# BOOST.net
KiCad netlist of a schematic drawn in Altium Designer
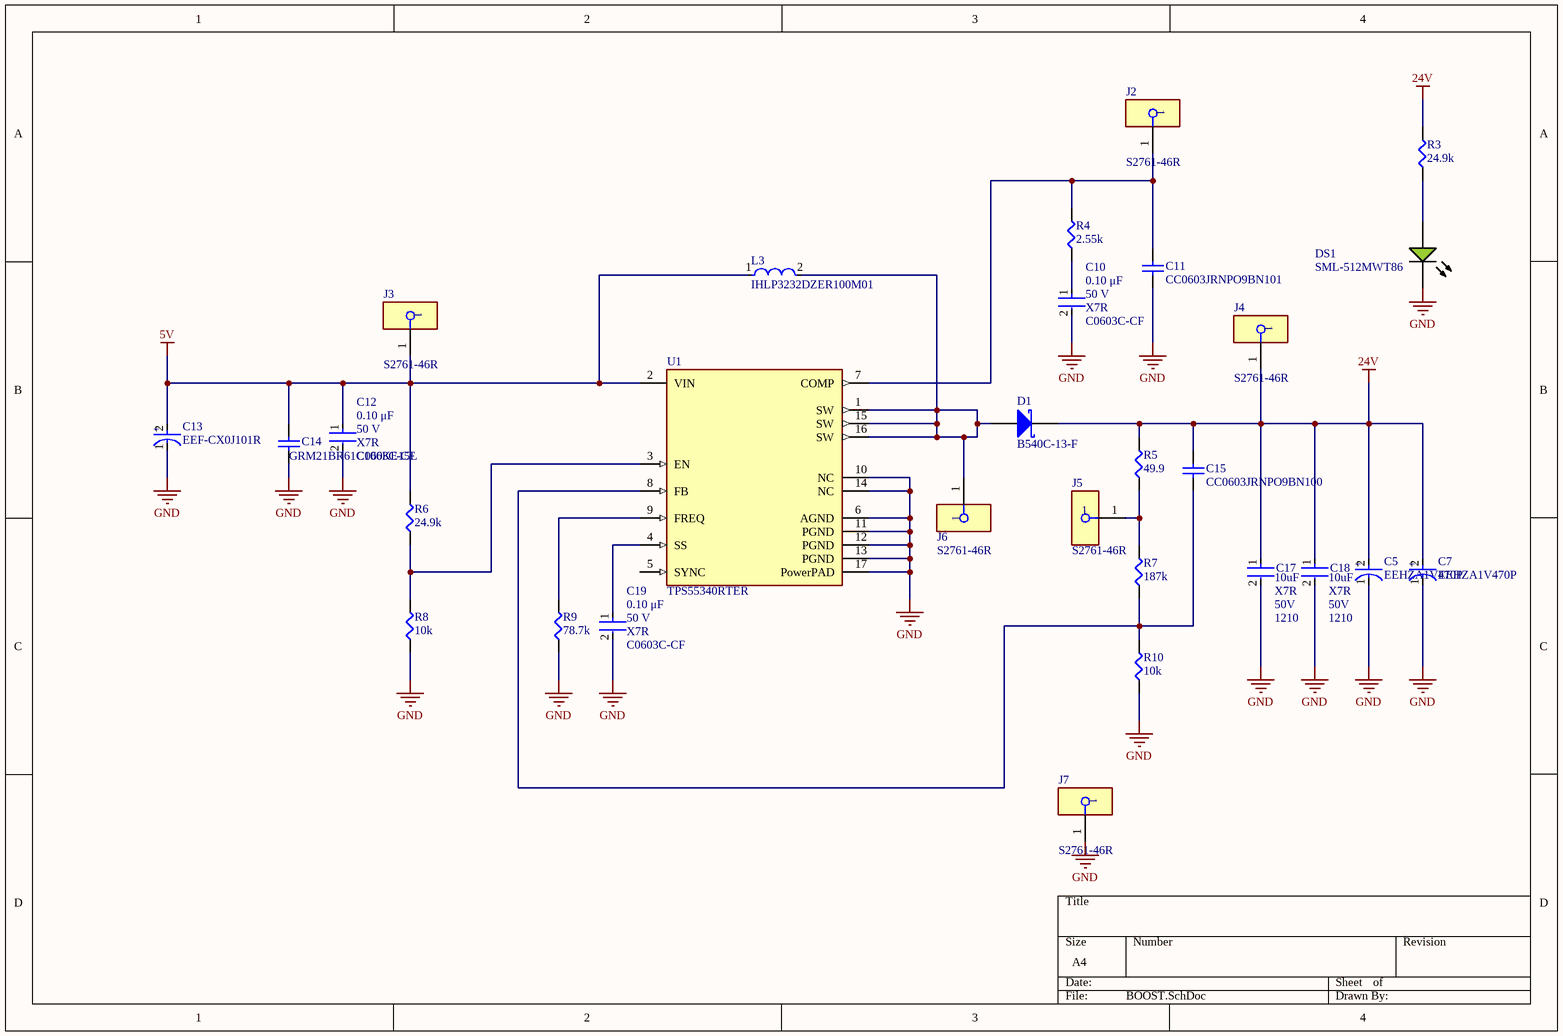
[diagram p0: BOOST.SchDoc]

(export (version "E")
  (design (tool "Eeschema 10.0.6"))
  (components
    (comp (ref "C5")
      (value "EEHZA1V470P")
      (footprint "FP-EEH-D-MFG")
      (description "Aluminum Hybrid Polymer Capacitors 47uF 20% 35V Life 10000Hours AEC-Q200 RADIAL SMT")
      (libsource (lib "Altium Content Vault") (part "a00bbbee19879c290e62620ae7e47b1"))
    )
    (comp (ref "C7")
      (value "EEHZA1V470P")
      (footprint "FP-EEH-D-MFG")
      (description "Aluminum Hybrid Polymer Capacitors 47uF 20% 35V Life 10000Hours AEC-Q200 RADIAL SMT")
      (libsource (lib "Altium Content Vault") (part "a00bbbee19879c290e62620ae7e47b1"))
    )
    (comp (ref "C10")
      (value "0.10 μF")
      (footprint "FP-C0603C-CF-MFG")
      (description "CAP CER 0.1UF 50V X7R 0603")
      (fields
        (field (name "TOLERANCE") "0.1")
        (field (name "MANUFACTURER") "KEMET")
        (field (name "PACKAGE") "C0603C-CF")
        (field (name "VOLTAGE RATING") "50 V")
        (field (name "TEMPERATURE CHARACTERISTIC") "X7R")
      )
      (libsource (lib "Altium Content Vault") (part "b4654b650e69147ec39a6b967a45e02"))
    )
    (comp (ref "C11")
      (value "CC0603JRNPO9BN101")
      (footprint "CAPC1608X90X40ML10T20")
      (description "Chip Capacitor, 100 pF, +/- 5%, 50 V, -55 to 125 degC, 0603 (1608 Metric), RoHS, Tape and Reel")
      (fields (field (name "TOLERANCE") "5%") (field (name "VOLTAGE") "50V"))
      (libsource (lib "Altium Content Vault") (part "CAP-NP-2"))
    )
    (comp (ref "C12")
      (value "0.10 μF")
      (footprint "FP-C0603C-CF-MFG")
      (description "CAP CER 0.1UF 50V X7R 0603")
      (fields
        (field (name "TOLERANCE") "0.1")
        (field (name "MANUFACTURER") "KEMET")
        (field (name "PACKAGE") "C0603C-CF")
        (field (name "VOLTAGE RATING") "50 V")
        (field (name "TEMPERATURE CHARACTERISTIC") "X7R")
      )
      (libsource (lib "Altium Content Vault") (part "b4654b650e69147ec39a6b967a45e02"))
    )
    (comp (ref "C13")
      (value "EEF-CX0J101R")
      (footprint "FP-CX-MFG")
      (description "CAP ALUM POLY 100UF 20% 6.3V SMD")
      (fields (field (name "VOLTAGE") "6.3V") (field (name "TOLERANCE") "20%"))
      (libsource (lib "Altium Content Vault") (part "a00bbbee19879c290e62620ae7e47b1"))
    )
    (comp (ref "C14")
      (value "GRM21BR61C106KE15L")
      (footprint "CAPC2013X135X50LL10T20")
      (fields (field (name "MANUFACTURER") "Murata"))
      (libsource (lib "Altium Content Vault") (part "CAP"))
    )
    (comp (ref "C15")
      (value "CC0603JRNPO9BN100")
      (footprint "CAPC1608X90X40ML10T20")
      (description "Chip Capacitor, 10 pF, +/- 5%, 50 V, -55 to 125 degC, 0603 (1608 Metric), RoHS, Tape and Reel")
      (fields (field (name "VOLTAGE") "50V") (field (name "TOLERANCE") "5%"))
      (libsource (lib "Altium Content Vault") (part "CAP-NP-2"))
    )
    (comp (ref "C17")
      (value "CL32B106KBJNNNE")
      (footprint "FP-CL32-IPC_C")
      (description "Cap Ceramic 10uF 50V X7R ±10% SMD 1210 +125°C Embossed T/R")
      (fields
        (field (name "CAPACITANCE") "10uF")
        (field (name "DIELECTRIC") "X7R")
        (field (name "VOLTAGE RATING (DC)") "50V")
        (field (name "CASE CODE (IMPERIAL)") "1210")
        (field (name "TOLERANCE") "10%")
        (field (name "VOLTAGE") "50V")
      )
      (libsource (lib "Altium Content Vault") (part "b4654b650e69147ec39a6b967a45e02"))
    )
    (comp (ref "C18")
      (value "CL32B106KBJNNNE")
      (footprint "FP-CL32-IPC_C")
      (description "Cap Ceramic 10uF 50V X7R ±10% SMD 1210 +125°C Embossed T/R")
      (fields
        (field (name "CAPACITANCE") "10uF")
        (field (name "DIELECTRIC") "X7R")
        (field (name "VOLTAGE RATING (DC)") "50V")
        (field (name "CASE CODE (IMPERIAL)") "1210")
        (field (name "TOLERANCE") "10%")
        (field (name "VOLTAGE") "50V")
      )
      (libsource (lib "Altium Content Vault") (part "b4654b650e69147ec39a6b967a45e02"))
    )
    (comp (ref "C19")
      (value "0.10 μF")
      (footprint "FP-C0603C-CF-MFG")
      (description "CAP CER 0.1UF 50V X7R 0603")
      (fields
        (field (name "TOLERANCE") "0.1")
        (field (name "MANUFACTURER") "KEMET")
        (field (name "PACKAGE") "C0603C-CF")
        (field (name "VOLTAGE RATING") "50 V")
        (field (name "TEMPERATURE CHARACTERISTIC") "X7R")
      )
      (libsource (lib "Altium Content Vault") (part "b4654b650e69147ec39a6b967a45e02"))
    )
    (comp (ref "D1")
      (value "B540C-13-F")
      (footprint "DIOD-B5X0C-2_L")
      (description "Schottky Barrier Rectifier, 5 A, 40 V, -55 to 125 degC, 2-Pin SMD, RoHS, Tape and Reel")
      (fields (field (name "MANUFACTURER") "DiodesIncorporated"))
      (libsource (lib "Altium Content Vault") (part "DSKY-KA-2"))
    )
    (comp (ref "DS1")
      (value "SML-512MWT86")
      (footprint "ROHM-SML-51X_V")
      (description "Yellow Green LED, 2.1 V, 20 mA, -30 to 85 degC, 2-Pin SMD, RoHS, Tape and Reel")
      (fields (field (name "MANUFACTURER") "Rohm"))
      (libsource (lib "Altium Content Vault") (part "LED-YELLOW-GREEN-AK-2"))
    )
    (comp (ref "J2")
      (value "S2761-46R")
      (footprint "FP-S2761-46R-MFG")
      (description "PC TEST POINT NATURAL")
      (libsource (lib "") (part "98815daf2f2c152b0c43f5ab9800df6_2"))
    )
    (comp (ref "J3")
      (value "S2761-46R")
      (footprint "FP-S2761-46R-MFG")
      (description "PC TEST POINT NATURAL")
      (libsource (lib "") (part "98815daf2f2c152b0c43f5ab9800df6_2"))
    )
    (comp (ref "J4")
      (value "S2761-46R")
      (footprint "FP-S2761-46R-MFG")
      (description "PC TEST POINT NATURAL")
      (libsource (lib "") (part "98815daf2f2c152b0c43f5ab9800df6_2"))
    )
    (comp (ref "J5")
      (value "S2761-46R")
      (footprint "FP-S2761-46R-MFG")
      (description "PC TEST POINT NATURAL")
      (libsource (lib "") (part "98815daf2f2c152b0c43f5ab9800df6_1"))
    )
    (comp (ref "J6")
      (value "S2761-46R")
      (footprint "FP-S2761-46R-MFG")
      (description "PC TEST POINT NATURAL")
      (libsource (lib "Altium Content Vault") (part "98815daf2f2c152b0c43f5ab9800df6"))
    )
    (comp (ref "J7")
      (value "S2761-46R")
      (footprint "FP-S2761-46R-MFG")
      (description "PC TEST POINT NATURAL")
      (libsource (lib "") (part "98815daf2f2c152b0c43f5ab9800df6_2"))
    )
    (comp (ref "L3")
      (value "IHLP3232DZER100M01")
      (footprint "FP-IHLP-3232DZ-FP_2_413x5-MFG")
      (description "FIXED IND 10UH 5.2A 59.9 MOHM")
      (fields (field (name "TOLERANCE") "20%"))
      (libsource (lib "Altium Content Vault") (part "725321dda6339637d4d059423bc1c3c"))
    )
    (comp (ref "R3")
      (value "24.9k")
      (footprint "SMD-0603-RES")
      (description "RES SMD 24.9K OHM 1% 1/10W 0603")
      (fields
        (field (name "PART NUMBER") "ERJ-3EKF2492V")
        (field (name "DIGI-KEY PART NUMBER") "P24.9KHCT-ND")
      )
      (libsource (lib "Panasonic_ERJ_0603") (part "ERJ-3EKF2492V"))
    )
    (comp (ref "R4")
      (value "2.55k")
      (footprint "SMD-0603-RES")
      (description "RES SMD 2.55K OHM 1% 1/10W 0603")
      (fields
        (field (name "PART NUMBER") "ERJ-3EKF2551V")
        (field (name "DIGI-KEY PART NUMBER") "P2.55KHCT-ND")
      )
      (libsource (lib "Panasonic_ERJ_0603") (part "ERJ-3EKF2551V"))
    )
    (comp (ref "R5")
      (value "49.9")
      (footprint "SMD-0603-RES")
      (description "RES SMD 49.9 OHM 1% 1/10W 0603")
      (fields
        (field (name "PART NUMBER") "ERJ-3EKF49R9V")
        (field (name "DIGI-KEY PART NUMBER") "P49.9HCT-ND")
      )
      (libsource (lib "Panasonic_ERJ_0603") (part "ERJ-3EKF49R9V"))
    )
    (comp (ref "R6")
      (value "24.9k")
      (footprint "SMD-0603-RES")
      (description "RES SMD 24.9K OHM 1% 1/10W 0603")
      (fields
        (field (name "PART NUMBER") "ERJ-3EKF2492V")
        (field (name "DIGI-KEY PART NUMBER") "P24.9KHCT-ND")
      )
      (libsource (lib "Panasonic_ERJ_0603") (part "ERJ-3EKF2492V"))
    )
    (comp (ref "R7")
      (value "187k")
      (footprint "SMD-0603-RES")
      (description "RES SMD 187K OHM 1% 1/10W 0603")
      (fields
        (field (name "PART NUMBER") "ERJ-3EKF1873V")
        (field (name "DIGI-KEY PART NUMBER") "P187KHCT-ND")
      )
      (libsource (lib "Panasonic_ERJ_0603") (part "ERJ-3EKF1873V"))
    )
    (comp (ref "R8")
      (value "10k")
      (footprint "SMD-0603-RES")
      (description "RES SMD 10K OHM 1% 1/10W 0603")
      (fields
        (field (name "PART NUMBER") "ERJ-3EKF1002V")
        (field (name "DIGI-KEY PART NUMBER") "P10.0KHCT-ND")
      )
      (libsource (lib "Panasonic_ERJ_0603") (part "ERJ-3EKF1002V"))
    )
    (comp (ref "R9")
      (value "78.7k")
      (footprint "SMD-0603-RES")
      (description "RES SMD 78.7K OHM 1% 1/10W 0603")
      (fields
        (field (name "PART NUMBER") "ERJ-3EKF7872V")
        (field (name "DIGI-KEY PART NUMBER") "P78.7KHCT-ND")
      )
      (libsource (lib "Panasonic_ERJ_0603") (part "ERJ-3EKF7872V"))
    )
    (comp (ref "R10")
      (value "10k")
      (footprint "SMD-0603-RES")
      (description "RES SMD 10K OHM 1% 1/10W 0603")
      (fields
        (field (name "PART NUMBER") "ERJ-3EKF1002V")
        (field (name "DIGI-KEY PART NUMBER") "P10.0KHCT-ND")
      )
      (libsource (lib "Panasonic_ERJ_0603") (part "ERJ-3EKF1002V"))
    )
    (comp (ref "U1")
      (value "TPS55340RTER")
      (footprint "FP-RTE0016C-IPC_A")
      (description "IC REG BOOST ADJ 5.25A 16WQFN")
      (libsource (lib "Altium Content Vault") (part "97752be00374b74295015ec96ff4d5f"))
    )
  )
  (nets
    (net (code "1") (name "5V") (class "Default")
      (node (ref "C12") (pin "1") (pinfunction "1_1") (pintype "passive"))
      (node (ref "C13") (pin "2") (pinfunction "A_2") (pintype "passive"))
      (node (ref "C14") (pin "2") (pinfunction "2_2") (pintype "passive"))
      (node (ref "J3") (pin "1") (pinfunction "1_1") (pintype "passive"))
      (node (ref "L3") (pin "1") (pinfunction "1_1") (pintype "passive"))
      (node (ref "R6") (pin "2") (pinfunction "2_2") (pintype "passive"))
      (node (ref "U1") (pin "2") (pinfunction "VIN_2") (pintype "power_in"))
    )
    (net (code "2") (name "24V") (class "Default")
      (node (ref "C15") (pin "1") (pinfunction "1_1") (pintype "passive"))
      (node (ref "C17") (pin "1") (pinfunction "1_1") (pintype "passive"))
      (node (ref "C18") (pin "1") (pinfunction "1_1") (pintype "passive"))
      (node (ref "C5") (pin "2") (pinfunction "A_2") (pintype "passive"))
      (node (ref "C7") (pin "2") (pinfunction "A_2") (pintype "passive"))
      (node (ref "D1") (pin "1") (pinfunction "K_1") (pintype "passive"))
      (node (ref "J4") (pin "1") (pinfunction "1_1") (pintype "passive"))
      (node (ref "R3") (pin "2") (pinfunction "2_2") (pintype "passive"))
      (node (ref "R5") (pin "2") (pinfunction "2_2") (pintype "passive"))
    )
    (net (code "3") (name "GND") (class "Default")
      (node (ref "C10") (pin "2") (pinfunction "2_2") (pintype "passive"))
      (node (ref "C11") (pin "1") (pinfunction "1_1") (pintype "passive"))
      (node (ref "C12") (pin "2") (pinfunction "2_2") (pintype "passive"))
      (node (ref "C13") (pin "1") (pinfunction "C_1") (pintype "passive"))
      (node (ref "C14") (pin "1") (pinfunction "1_1") (pintype "passive"))
      (node (ref "C17") (pin "2") (pinfunction "2_2") (pintype "passive"))
      (node (ref "C18") (pin "2") (pinfunction "2_2") (pintype "passive"))
      (node (ref "C19") (pin "2") (pinfunction "2_2") (pintype "passive"))
      (node (ref "C5") (pin "1") (pinfunction "C_1") (pintype "passive"))
      (node (ref "C7") (pin "1") (pinfunction "C_1") (pintype "passive"))
      (node (ref "DS1") (pin "2") (pinfunction "K_2") (pintype "passive"))
      (node (ref "J7") (pin "1") (pinfunction "1_1") (pintype "passive"))
      (node (ref "R10") (pin "1") (pinfunction "1_1") (pintype "passive"))
      (node (ref "R8") (pin "1") (pinfunction "1_1") (pintype "passive"))
      (node (ref "R9") (pin "1") (pinfunction "1_1") (pintype "passive"))
      (node (ref "U1") (pin "10") (pinfunction "NC_10") (pintype "passive"))
      (node (ref "U1") (pin "11") (pinfunction "PGND_11") (pintype "power_in"))
      (node (ref "U1") (pin "12") (pinfunction "PGND_12") (pintype "power_in"))
      (node (ref "U1") (pin "13") (pinfunction "PGND_13") (pintype "power_in"))
      (node (ref "U1") (pin "14") (pinfunction "NC_14") (pintype "passive"))
      (node (ref "U1") (pin "17") (pinfunction "PowerPAD_17") (pintype "power_in"))
      (node (ref "U1") (pin "6") (pinfunction "AGND_6") (pintype "power_in"))
    )
    (net (code "4") (name "Net-(C10-Pad1)") (class "Default")
      (node (ref "C10") (pin "1") (pinfunction "1_1") (pintype "passive"))
      (node (ref "R4") (pin "1") (pinfunction "1_1") (pintype "passive"))
    )
    (net (code "5") (name "Net-(D1-A)") (class "Default")
      (node (ref "D1") (pin "2") (pinfunction "A_2") (pintype "passive"))
      (node (ref "J6") (pin "1") (pinfunction "1_1") (pintype "passive"))
      (node (ref "L3") (pin "2") (pinfunction "2_2") (pintype "passive"))
      (node (ref "U1") (pin "1") (pinfunction "SW_1") (pintype "output"))
      (node (ref "U1") (pin "15") (pinfunction "SW_15") (pintype "output"))
      (node (ref "U1") (pin "16") (pinfunction "SW_16") (pintype "output"))
    )
    (net (code "6") (name "Net-(DS1-A)") (class "Default")
      (node (ref "DS1") (pin "1") (pinfunction "A_1") (pintype "passive"))
      (node (ref "R3") (pin "1") (pinfunction "1_1") (pintype "passive"))
    )
    (net (code "7") (name "Net-(J5-Pad1)") (class "Default")
      (node (ref "J5") (pin "1") (pinfunction "1_1") (pintype "passive"))
      (node (ref "R5") (pin "1") (pinfunction "1_1") (pintype "passive"))
      (node (ref "R7") (pin "2") (pinfunction "2_2") (pintype "passive"))
    )
    (net (code "8") (name "Net-(U1-COMP)") (class "Default")
      (node (ref "C11") (pin "2") (pinfunction "2_2") (pintype "passive"))
      (node (ref "J2") (pin "1") (pinfunction "1_1") (pintype "passive"))
      (node (ref "R4") (pin "2") (pinfunction "2_2") (pintype "passive"))
      (node (ref "U1") (pin "7") (pinfunction "COMP_7") (pintype "output"))
    )
    (net (code "9") (name "Net-(U1-EN)") (class "Default")
      (node (ref "R6") (pin "1") (pinfunction "1_1") (pintype "passive"))
      (node (ref "R8") (pin "2") (pinfunction "2_2") (pintype "passive"))
      (node (ref "U1") (pin "3") (pinfunction "EN_3") (pintype "input"))
    )
    (net (code "10") (name "Net-(U1-FB)") (class "Default")
      (node (ref "C15") (pin "2") (pinfunction "2_2") (pintype "passive"))
      (node (ref "R10") (pin "2") (pinfunction "2_2") (pintype "passive"))
      (node (ref "R7") (pin "1") (pinfunction "1_1") (pintype "passive"))
      (node (ref "U1") (pin "8") (pinfunction "FB_8") (pintype "input"))
    )
    (net (code "11") (name "Net-(U1-FREQ)") (class "Default")
      (node (ref "R9") (pin "2") (pinfunction "2_2") (pintype "passive"))
      (node (ref "U1") (pin "9") (pinfunction "FREQ_9") (pintype "input"))
    )
    (net (code "12") (name "Net-(U1-SS)") (class "Default")
      (node (ref "C19") (pin "1") (pinfunction "1_1") (pintype "passive"))
      (node (ref "U1") (pin "4") (pinfunction "SS_4") (pintype "input"))
    )
    (net (code "13") (name "unconnected-(U1-SYNC-Pad5)") (class "Default")
      (node (ref "U1") (pin "5") (pinfunction "SYNC_5") (pintype "input"))
    )
  )
)
